# RPi_Zero_W_Breakout_0_3.net
KiCad netlist of a schematic drawn in EAGLE
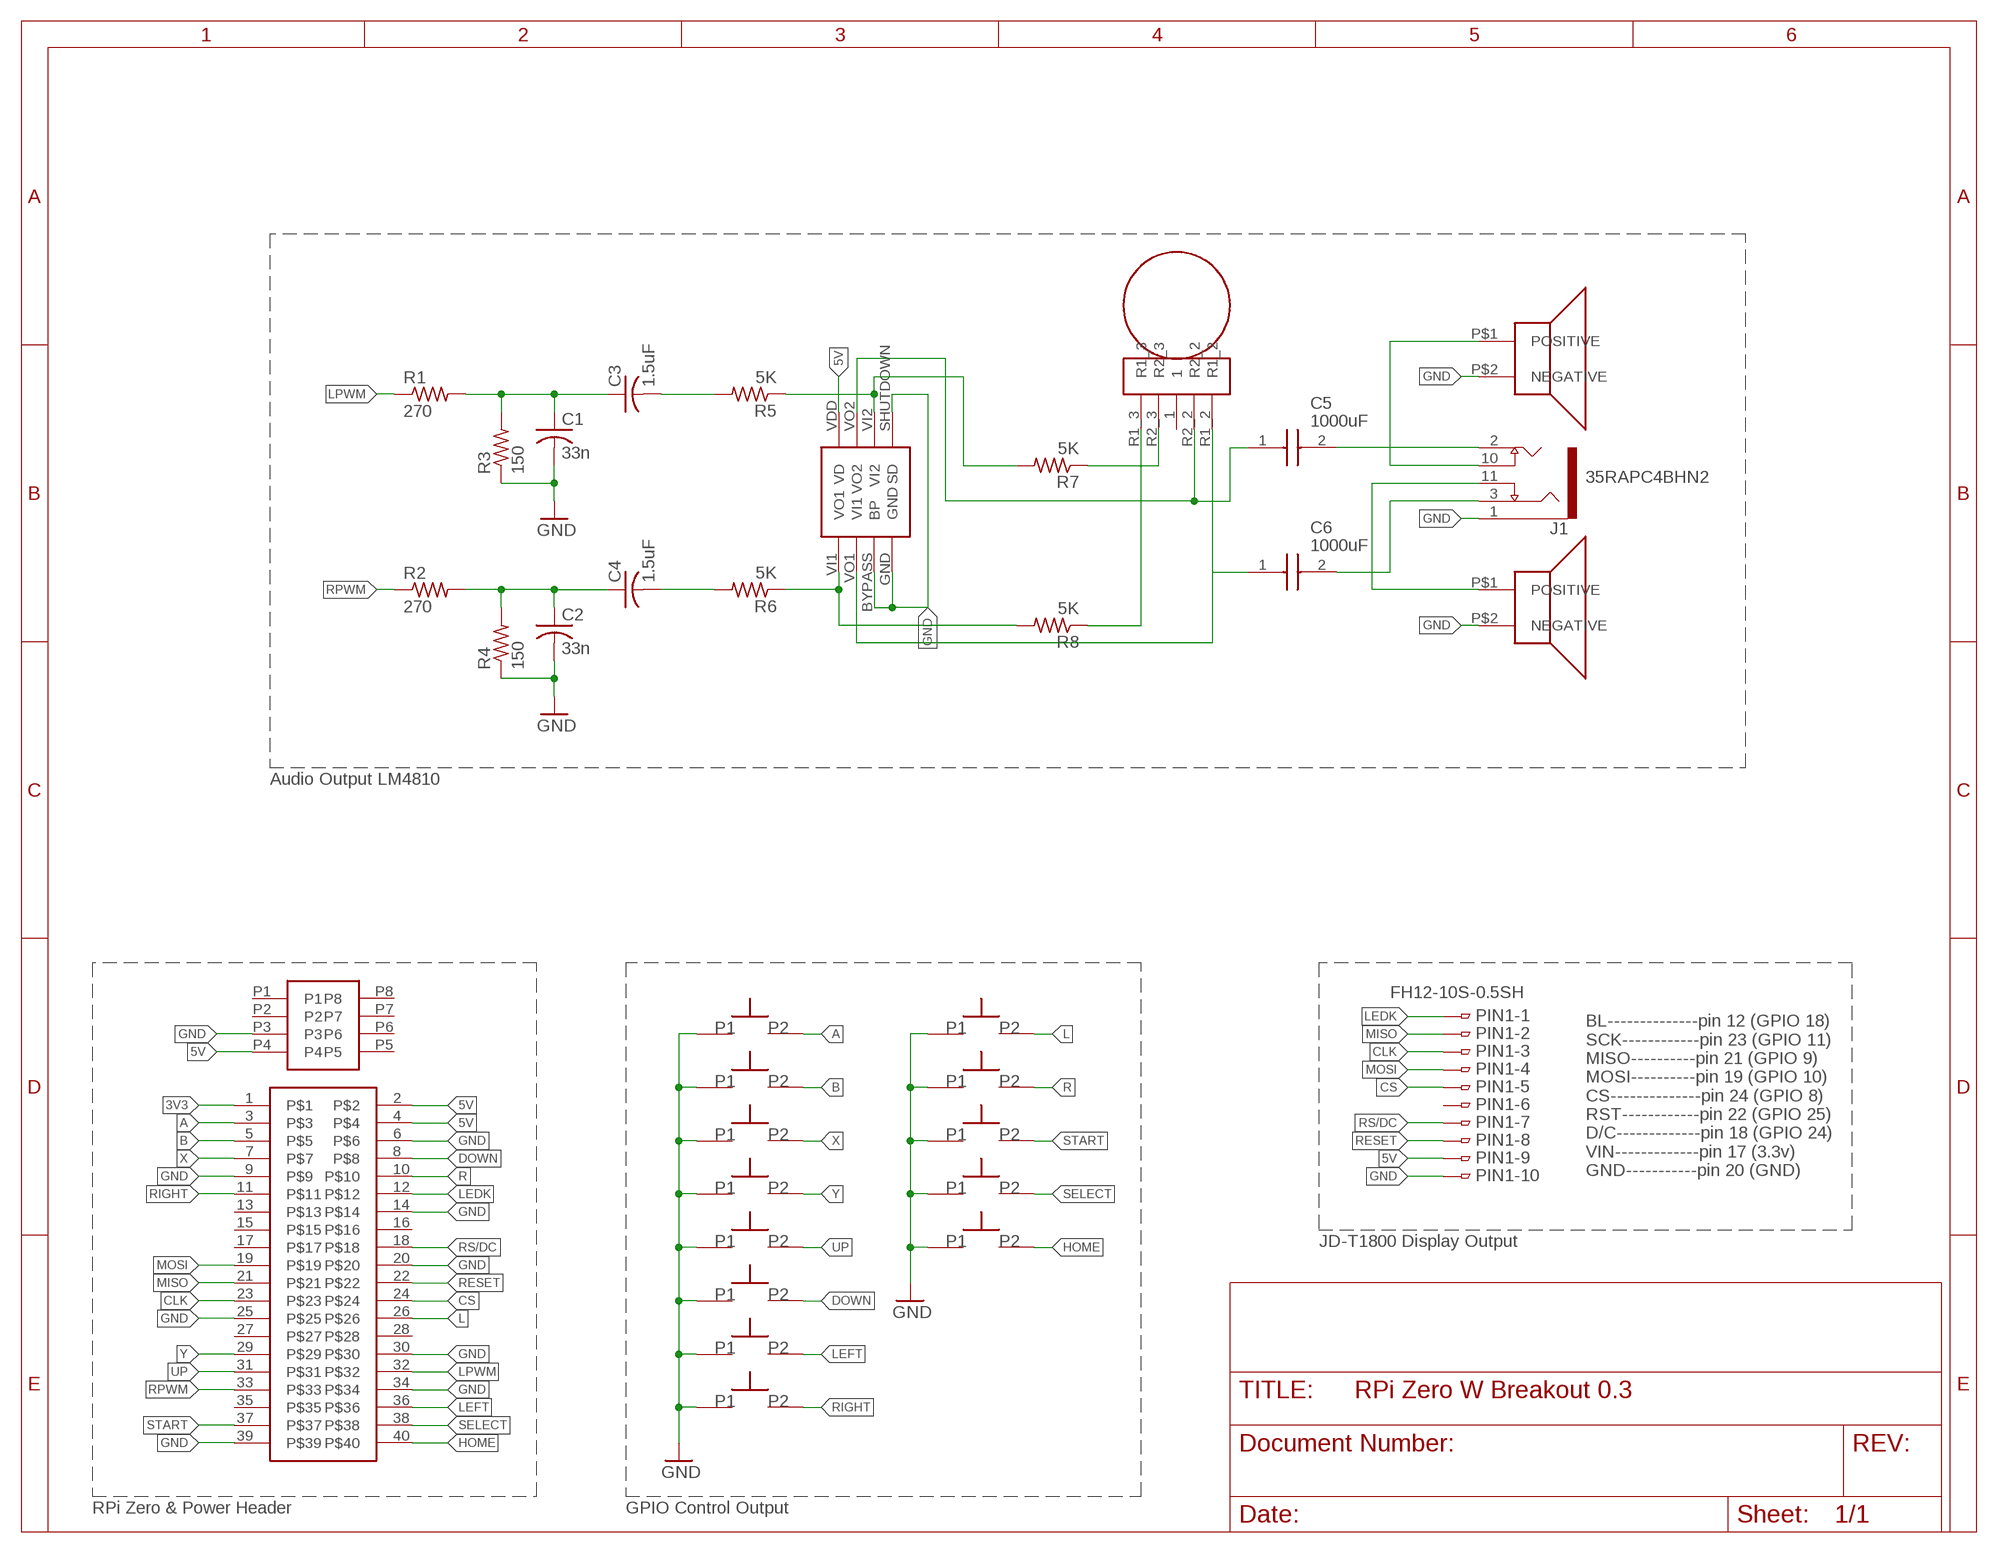
[diagram p0: schematic, sheet 1]

(export (version "E")
  (design (tool "Eeschema 10.0.6"))
  (components
    (comp (ref "A")
      (value "SPST_TACTILE_SWITCH")
      (footprint "eagle-import:SPST_TACTILESWITCH_TL3301PF160QG")
      (libsource (lib "eagle-import") (part "SPST_TACTILE_SWITCH"))
    )
    (comp (ref "B")
      (value "SPST_TACTILESWITCH_TL3301PF160QG")
      (footprint "eagle-import:SPST_TACTILESWITCH_TL3301PF160QG")
      (libsource (lib "eagle-import") (part "SPST_TACTILESWITCH_TL3301PF160QG"))
    )
    (comp (ref "C1")
      (value "33n")
      (footprint "eagle-import:C0805K")
      (libsource (lib "eagle-import") (part "C-USC0805K"))
    )
    (comp (ref "C2")
      (value "33n")
      (footprint "eagle-import:C0805K")
      (libsource (lib "eagle-import") (part "C-USC0805K"))
    )
    (comp (ref "C3")
      (value "1.5uF")
      (footprint "eagle-import:C0805K")
      (libsource (lib "eagle-import") (part "C-USC0805K"))
    )
    (comp (ref "C4")
      (value "1.5uF")
      (footprint "eagle-import:C0805K")
      (libsource (lib "eagle-import") (part "C-USC0805K"))
    )
    (comp (ref "C5")
      (value "1000uF")
      (footprint "eagle-import:UWT(8X10)")
      (fields
        (field (name "MANUFACTURER_PART_NUMBER") "UWT0J102MNL1GS")
        (field (name "MOUSER_PART_NUMBER") "647-UWT0J102MNL1S")
      )
      (libsource (lib "eagle-import") (part "UWT0J102MNL1GS"))
    )
    (comp (ref "C6")
      (value "1000uF")
      (footprint "eagle-import:UWT(8X10)")
      (fields
        (field (name "MANUFACTURER_PART_NUMBER") "UWT0J102MNL1GS")
        (field (name "MOUSER_PART_NUMBER") "647-UWT0J102MNL1S")
      )
      (libsource (lib "eagle-import") (part "UWT0J102MNL1GS"))
    )
    (comp (ref "DOWN")
      (value "SPST_TACTILESWITCH_TL3301PF160QG")
      (footprint "eagle-import:SPST_TACTILESWITCH_TL3301PF160QG")
      (libsource (lib "eagle-import") (part "SPST_TACTILESWITCH_TL3301PF160QG"))
    )
    (comp (ref "HOME")
      (value "SPST_TACTILESWITCH_TL3301PF160QG")
      (footprint "eagle-import:SPST_TACTILESWITCH_TL3301PF160QG")
      (libsource (lib "eagle-import") (part "SPST_TACTILESWITCH_TL3301PF160QG"))
    )
    (comp (ref "J1")
      (value "35RAPC4BHN2")
      (footprint "eagle-import:SWITCHCRAFT_35RAPC4BHN2")
      (fields (field (name "DIGI-KEY_PART_NUMBER") "SC1459-ND") (field (name "MF") "Switchcraft"))
      (libsource (lib "eagle-import") (part "35RAPC4BHN2"))
    )
    (comp (ref "LEFT")
      (value "SPST_TACTILESWITCH_TL3301PF160QG")
      (footprint "eagle-import:SPST_TACTILESWITCH_TL3301PF160QG")
      (libsource (lib "eagle-import") (part "SPST_TACTILESWITCH_TL3301PF160QG"))
    )
    (comp (ref "LSPK")
      (value "SP-1208")
      (footprint "eagle-import:SP-1208")
      (libsource (lib "eagle-import") (part "SP-1208"))
    )
    (comp (ref "PIN1")
      (value "FH12-10S-0.5SH")
      (footprint "eagle-import:FH12-10S-0.5SH")
      (fields (field (name "MPN") "FH12-10S-0.5SH(55)"))
      (libsource (lib "eagle-import") (part "FH12-10S-0.5SH"))
    )
    (comp (ref "R1")
      (value "270")
      (footprint "eagle-import:R0805")
      (libsource (lib "eagle-import") (part "R-US_R0805"))
    )
    (comp (ref "R2")
      (value "270")
      (footprint "eagle-import:R0805")
      (libsource (lib "eagle-import") (part "R-US_R0805"))
    )
    (comp (ref "R3")
      (value "150")
      (footprint "eagle-import:R0805")
      (libsource (lib "eagle-import") (part "R-US_R0805"))
    )
    (comp (ref "R4")
      (value "150")
      (footprint "eagle-import:R0805")
      (libsource (lib "eagle-import") (part "R-US_R0805"))
    )
    (comp (ref "R5")
      (value "5K")
      (footprint "eagle-import:R0805")
      (libsource (lib "eagle-import") (part "R-US_R0805"))
    )
    (comp (ref "R6")
      (value "5K")
      (footprint "eagle-import:R0805")
      (libsource (lib "eagle-import") (part "R-US_R0805"))
    )
    (comp (ref "R7")
      (value "5K")
      (footprint "eagle-import:R0805")
      (libsource (lib "eagle-import") (part "R-US_R0805"))
    )
    (comp (ref "R8")
      (value "5K")
      (footprint "eagle-import:R0805")
      (libsource (lib "eagle-import") (part "R-US_R0805"))
    )
    (comp (ref "RF")
      (value "RK14J12A0A0K")
      (footprint "eagle-import:RK14J12A0A0K")
      (libsource (lib "eagle-import") (part "RK14J12A0A0K"))
    )
    (comp (ref "RIGHT")
      (value "SPST_TACTILESWITCH_TL3301PF160QG")
      (footprint "eagle-import:SPST_TACTILESWITCH_TL3301PF160QG")
      (libsource (lib "eagle-import") (part "SPST_TACTILESWITCH_TL3301PF160QG"))
    )
    (comp (ref "RSPK")
      (value "SP-1208")
      (footprint "eagle-import:SP-1208")
      (libsource (lib "eagle-import") (part "SP-1208"))
    )
    (comp (ref "SELECT")
      (value "SPST_TACTILESWITCH_TL3301PF160QG")
      (footprint "eagle-import:SPST_TACTILESWITCH_TL3301PF160QG")
      (libsource (lib "eagle-import") (part "SPST_TACTILESWITCH_TL3301PF160QG"))
    )
    (comp (ref "START")
      (value "SPST_TACTILE_SWITCH")
      (footprint "eagle-import:SPST_TACTILESWITCH_TL3301PF160QG")
      (libsource (lib "eagle-import") (part "SPST_TACTILE_SWITCH"))
    )
    (comp (ref "U$1")
      (value "RPI_ZERO")
      (footprint "eagle-import:RPI_ZERO")
      (libsource (lib "eagle-import") (part "RPI_ZERO"))
    )
    (comp (ref "U$2")
      (value "LM4810MM/NOPBCT-ND")
      (footprint "eagle-import:NOPBCT-ND")
      (libsource (lib "eagle-import") (part "LM4810MM/NOPBCT-ND"))
    )
    (comp (ref "U$3")
      (value "M22-6340442")
      (footprint "eagle-import:M22-6340442")
      (libsource (lib "eagle-import") (part "M22-6340442"))
    )
    (comp (ref "U$4")
      (value "SPST_TACTILE_SWITCHRIGHTANGLEBENT")
      (footprint "eagle-import:SPST_TACTILESWITCH_TL3360CF185Q_BENTFRAME")
      (fields (field (name "SPICEPREFIX") "B"))
      (libsource (lib "eagle-import") (part "SPST_TACTILE_SWITCHRIGHTANGLEBENT"))
    )
    (comp (ref "U$5")
      (value "SPST_TACTILE_SWITCHRIGHTANGLEBENT")
      (footprint "eagle-import:SPST_TACTILESWITCH_TL3360CF185Q_BENTFRAME")
      (fields (field (name "SPICEPREFIX") "B"))
      (libsource (lib "eagle-import") (part "SPST_TACTILE_SWITCHRIGHTANGLEBENT"))
    )
    (comp (ref "UP")
      (value "SPST_TACTILESWITCH_TL3301PF160QG")
      (footprint "eagle-import:SPST_TACTILESWITCH_TL3301PF160QG")
      (libsource (lib "eagle-import") (part "SPST_TACTILESWITCH_TL3301PF160QG"))
    )
    (comp (ref "X")
      (value "SPST_TACTILESWITCH_TL3301PF160QG")
      (footprint "eagle-import:SPST_TACTILESWITCH_TL3301PF160QG")
      (libsource (lib "eagle-import") (part "SPST_TACTILESWITCH_TL3301PF160QG"))
    )
    (comp (ref "Y")
      (value "SPST_TACTILESWITCH_TL3301PF160QG")
      (footprint "eagle-import:SPST_TACTILESWITCH_TL3301PF160QG")
      (libsource (lib "eagle-import") (part "SPST_TACTILESWITCH_TL3301PF160QG"))
    )
  )
  (nets
    (net (code "1") (name "3V3") (class "Default")
      (node (ref "U$1") (pin "1") (pinfunction "P$1_1") (pintype "bidirectional"))
    )
    (net (code "2") (name "5V") (class "Default")
      (node (ref "PIN1") (pin "9") (pinfunction "1_9") (pintype "passive"))
      (node (ref "U$1") (pin "2") (pinfunction "P$2_2") (pintype "bidirectional"))
      (node (ref "U$1") (pin "4") (pinfunction "P$4_4") (pintype "bidirectional"))
      (node (ref "U$2") (pin "VDD") (pinfunction "VD_VDD") (pintype "bidirectional"))
      (node (ref "U$3") (pin "P4") (pinfunction "P4_P4") (pintype "bidirectional"))
    )
    (net (code "3") (name "A") (class "Default")
      (node (ref "A") (pin "P$3") (pinfunction "P$2_P$3") (pintype "bidirectional"))
      (node (ref "U$1") (pin "3") (pinfunction "P$3_3") (pintype "bidirectional"))
    )
    (net (code "4") (name "B") (class "Default")
      (node (ref "B") (pin "P$3") (pinfunction "P$2_P$3") (pintype "bidirectional"))
      (node (ref "U$1") (pin "5") (pinfunction "P$5_5") (pintype "bidirectional"))
    )
    (net (code "5") (name "CLK") (class "Default")
      (node (ref "PIN1") (pin "3") (pinfunction "1_3") (pintype "passive"))
      (node (ref "U$1") (pin "23") (pinfunction "P$23_23") (pintype "bidirectional"))
    )
    (net (code "6") (name "CS") (class "Default")
      (node (ref "PIN1") (pin "5") (pinfunction "1_5") (pintype "passive"))
      (node (ref "U$1") (pin "24") (pinfunction "P$24_24") (pintype "bidirectional"))
    )
    (net (code "7") (name "DOWN") (class "Default")
      (node (ref "DOWN") (pin "P$3") (pinfunction "P$2_P$3") (pintype "bidirectional"))
      (node (ref "U$1") (pin "8") (pinfunction "P$8_8") (pintype "bidirectional"))
    )
    (net (code "8") (name "GND") (class "Default")
      (node (ref "A") (pin "P$1") (pinfunction "P$1_P$1") (pintype "bidirectional"))
      (node (ref "B") (pin "P$1") (pinfunction "P$1_P$1") (pintype "bidirectional"))
      (node (ref "C1") (pin "2") (pinfunction "2_2") (pintype "passive"))
      (node (ref "C2") (pin "2") (pinfunction "2_2") (pintype "passive"))
      (node (ref "DOWN") (pin "P$1") (pinfunction "P$1_P$1") (pintype "bidirectional"))
      (node (ref "HOME") (pin "P$1") (pinfunction "P$1_P$1") (pintype "bidirectional"))
      (node (ref "J1") (pin "1") (pinfunction "1_1") (pintype "passive"))
      (node (ref "LEFT") (pin "P$1") (pinfunction "P$1_P$1") (pintype "bidirectional"))
      (node (ref "LSPK") (pin "P$2") (pinfunction "NEGATIVE_P$2") (pintype "bidirectional"))
      (node (ref "PIN1") (pin "10") (pinfunction "1_10") (pintype "passive"))
      (node (ref "R3") (pin "1") (pinfunction "1_1") (pintype "passive"))
      (node (ref "R4") (pin "1") (pinfunction "1_1") (pintype "passive"))
      (node (ref "RIGHT") (pin "P$1") (pinfunction "P$1_P$1") (pintype "bidirectional"))
      (node (ref "RSPK") (pin "P$2") (pinfunction "NEGATIVE_P$2") (pintype "bidirectional"))
      (node (ref "SELECT") (pin "P$1") (pinfunction "P$1_P$1") (pintype "bidirectional"))
      (node (ref "START") (pin "P$1") (pinfunction "P$1_P$1") (pintype "bidirectional"))
      (node (ref "U$1") (pin "14") (pinfunction "P$14_14") (pintype "bidirectional"))
      (node (ref "U$1") (pin "20") (pinfunction "P$20_20") (pintype "bidirectional"))
      (node (ref "U$1") (pin "25") (pinfunction "P$25_25") (pintype "bidirectional"))
      (node (ref "U$1") (pin "30") (pinfunction "P$30_30") (pintype "bidirectional"))
      (node (ref "U$1") (pin "34") (pinfunction "P$34_34") (pintype "bidirectional"))
      (node (ref "U$1") (pin "39") (pinfunction "P$39_39") (pintype "bidirectional"))
      (node (ref "U$1") (pin "6") (pinfunction "P$6_6") (pintype "bidirectional"))
      (node (ref "U$1") (pin "9") (pinfunction "P$9_9") (pintype "bidirectional"))
      (node (ref "U$2") (pin "BYPASS") (pinfunction "BP_BYPASS") (pintype "bidirectional"))
      (node (ref "U$2") (pin "GND") (pinfunction "GND_GND") (pintype "bidirectional"))
      (node (ref "U$2") (pin "SHUTDOWN") (pinfunction "SD_SHUTDOWN") (pintype "bidirectional"))
      (node (ref "U$3") (pin "P3") (pinfunction "P3_P3") (pintype "bidirectional"))
      (node (ref "U$4") (pin "P$1") (pinfunction "P$1_P$1") (pintype "bidirectional"))
      (node (ref "U$5") (pin "P$1") (pinfunction "P$1_P$1") (pintype "bidirectional"))
      (node (ref "UP") (pin "P$1") (pinfunction "P$1_P$1") (pintype "bidirectional"))
      (node (ref "X") (pin "P$1") (pinfunction "P$1_P$1") (pintype "bidirectional"))
      (node (ref "Y") (pin "P$1") (pinfunction "P$1_P$1") (pintype "bidirectional"))
    )
    (net (code "9") (name "HOME") (class "Default")
      (node (ref "HOME") (pin "P$3") (pinfunction "P$2_P$3") (pintype "bidirectional"))
      (node (ref "U$1") (pin "40") (pinfunction "P$40_40") (pintype "bidirectional"))
    )
    (net (code "10") (name "L") (class "Default")
      (node (ref "U$1") (pin "26") (pinfunction "P$26_26") (pintype "bidirectional"))
      (node (ref "U$4") (pin "P$2") (pinfunction "P$2_P$2") (pintype "bidirectional"))
    )
    (net (code "11") (name "LEDK") (class "Default")
      (node (ref "PIN1") (pin "1") (pinfunction "1_1") (pintype "passive"))
      (node (ref "U$1") (pin "12") (pinfunction "P$12_12") (pintype "bidirectional"))
    )
    (net (code "12") (name "LEFT") (class "Default")
      (node (ref "LEFT") (pin "P$3") (pinfunction "P$2_P$3") (pintype "bidirectional"))
      (node (ref "U$1") (pin "36") (pinfunction "P$36_36") (pintype "bidirectional"))
    )
    (net (code "13") (name "LPWM") (class "Default")
      (node (ref "R1") (pin "1") (pinfunction "1_1") (pintype "passive"))
      (node (ref "U$1") (pin "32") (pinfunction "P$32_32") (pintype "bidirectional"))
    )
    (net (code "14") (name "MISO") (class "Default")
      (node (ref "PIN1") (pin "2") (pinfunction "1_2") (pintype "passive"))
      (node (ref "U$1") (pin "21") (pinfunction "P$21_21") (pintype "bidirectional"))
    )
    (net (code "15") (name "MOSI") (class "Default")
      (node (ref "PIN1") (pin "4") (pinfunction "1_4") (pintype "passive"))
      (node (ref "U$1") (pin "19") (pinfunction "P$19_19") (pintype "bidirectional"))
    )
    (net (code "16") (name "Net-(C1-Pad1)") (class "Default")
      (node (ref "C1") (pin "1") (pinfunction "1_1") (pintype "passive"))
      (node (ref "C3") (pin "1") (pinfunction "1_1") (pintype "passive"))
      (node (ref "R1") (pin "2") (pinfunction "2_2") (pintype "passive"))
      (node (ref "R3") (pin "2") (pinfunction "2_2") (pintype "passive"))
    )
    (net (code "17") (name "Net-(C2-Pad1)") (class "Default")
      (node (ref "C2") (pin "1") (pinfunction "1_1") (pintype "passive"))
      (node (ref "C4") (pin "1") (pinfunction "1_1") (pintype "passive"))
      (node (ref "R2") (pin "2") (pinfunction "2_2") (pintype "passive"))
      (node (ref "R4") (pin "2") (pinfunction "2_2") (pintype "passive"))
    )
    (net (code "18") (name "Net-(C3-Pad2)") (class "Default")
      (node (ref "C3") (pin "2") (pinfunction "2_2") (pintype "passive"))
      (node (ref "R5") (pin "2") (pinfunction "2_2") (pintype "passive"))
    )
    (net (code "19") (name "Net-(C4-Pad2)") (class "Default")
      (node (ref "C4") (pin "2") (pinfunction "2_2") (pintype "passive"))
      (node (ref "R6") (pin "2") (pinfunction "2_2") (pintype "passive"))
    )
    (net (code "20") (name "Net-(C5-+)") (class "Default")
      (node (ref "C5") (pin "1") (pinfunction "+_1") (pintype "bidirectional"))
      (node (ref "RF") (pin "R2_2") (pinfunction "R2_2_R2_2") (pintype "bidirectional"))
      (node (ref "U$2") (pin "VO2") (pinfunction "VO2_VO2") (pintype "bidirectional"))
    )
    (net (code "21") (name "Net-(C5--)") (class "Default")
      (node (ref "C5") (pin "2") (pinfunction "-_2") (pintype "bidirectional"))
      (node (ref "J1") (pin "2") (pinfunction "2_2") (pintype "passive"))
    )
    (net (code "22") (name "Net-(C6-+)") (class "Default")
      (node (ref "C6") (pin "1") (pinfunction "+_1") (pintype "bidirectional"))
      (node (ref "RF") (pin "R1_2") (pinfunction "R1_2_R1_2") (pintype "bidirectional"))
      (node (ref "U$2") (pin "VO1") (pinfunction "VI1_VO1") (pintype "bidirectional"))
    )
    (net (code "23") (name "Net-(C6--)") (class "Default")
      (node (ref "C6") (pin "2") (pinfunction "-_2") (pintype "bidirectional"))
      (node (ref "J1") (pin "3") (pinfunction "3_3") (pintype "passive"))
    )
    (net (code "24") (name "Net-(LSPK-POSITIVE)") (class "Default")
      (node (ref "J1") (pin "10") (pinfunction "10_10") (pintype "passive"))
      (node (ref "LSPK") (pin "P$1") (pinfunction "POSITIVE_P$1") (pintype "bidirectional"))
    )
    (net (code "25") (name "Net-(R5-Pad1)") (class "Default")
      (node (ref "R5") (pin "1") (pinfunction "1_1") (pintype "passive"))
      (node (ref "R7") (pin "2") (pinfunction "2_2") (pintype "passive"))
      (node (ref "U$2") (pin "VI2") (pinfunction "VI2_VI2") (pintype "bidirectional"))
    )
    (net (code "26") (name "Net-(R7-Pad1)") (class "Default")
      (node (ref "R7") (pin "1") (pinfunction "1_1") (pintype "passive"))
      (node (ref "RF") (pin "R2_3") (pinfunction "R2_3_R2_3") (pintype "bidirectional"))
    )
    (net (code "27") (name "Net-(R8-Pad1)") (class "Default")
      (node (ref "R8") (pin "1") (pinfunction "1_1") (pintype "passive"))
      (node (ref "RF") (pin "R1_3") (pinfunction "R1_3_R1_3") (pintype "bidirectional"))
    )
    (net (code "28") (name "Net-(RSPK-POSITIVE)") (class "Default")
      (node (ref "J1") (pin "11") (pinfunction "11_11") (pintype "passive"))
      (node (ref "RSPK") (pin "P$1") (pinfunction "POSITIVE_P$1") (pintype "bidirectional"))
    )
    (net (code "29") (name "Net-(U$2-VO1)") (class "Default")
      (node (ref "R6") (pin "1") (pinfunction "1_1") (pintype "passive"))
      (node (ref "R8") (pin "2") (pinfunction "2_2") (pintype "passive"))
      (node (ref "U$2") (pin "VI1") (pinfunction "VO1_VI1") (pintype "bidirectional"))
    )
    (net (code "30") (name "R") (class "Default")
      (node (ref "U$1") (pin "10") (pinfunction "P$10_10") (pintype "bidirectional"))
      (node (ref "U$5") (pin "P$2") (pinfunction "P$2_P$2") (pintype "bidirectional"))
    )
    (net (code "31") (name "RESET") (class "Default")
      (node (ref "PIN1") (pin "8") (pinfunction "1_8") (pintype "passive"))
      (node (ref "U$1") (pin "22") (pinfunction "P$22_22") (pintype "bidirectional"))
    )
    (net (code "32") (name "RIGHT") (class "Default")
      (node (ref "RIGHT") (pin "P$3") (pinfunction "P$2_P$3") (pintype "bidirectional"))
      (node (ref "U$1") (pin "11") (pinfunction "P$11_11") (pintype "bidirectional"))
    )
    (net (code "33") (name "RPWM") (class "Default")
      (node (ref "R2") (pin "1") (pinfunction "1_1") (pintype "passive"))
      (node (ref "U$1") (pin "33") (pinfunction "P$33_33") (pintype "bidirectional"))
    )
    (net (code "34") (name "RS{slash}DC") (class "Default")
      (node (ref "PIN1") (pin "7") (pinfunction "1_7") (pintype "passive"))
      (node (ref "U$1") (pin "18") (pinfunction "P$18_18") (pintype "bidirectional"))
    )
    (net (code "35") (name "SELECT") (class "Default")
      (node (ref "SELECT") (pin "P$3") (pinfunction "P$2_P$3") (pintype "bidirectional"))
      (node (ref "U$1") (pin "38") (pinfunction "P$38_38") (pintype "bidirectional"))
    )
    (net (code "36") (name "START") (class "Default")
      (node (ref "START") (pin "P$3") (pinfunction "P$2_P$3") (pintype "bidirectional"))
      (node (ref "U$1") (pin "37") (pinfunction "P$37_37") (pintype "bidirectional"))
    )
    (net (code "37") (name "UP") (class "Default")
      (node (ref "U$1") (pin "31") (pinfunction "P$31_31") (pintype "bidirectional"))
      (node (ref "UP") (pin "P$3") (pinfunction "P$2_P$3") (pintype "bidirectional"))
    )
    (net (code "38") (name "X") (class "Default")
      (node (ref "U$1") (pin "7") (pinfunction "P$7_7") (pintype "bidirectional"))
      (node (ref "X") (pin "P$3") (pinfunction "P$2_P$3") (pintype "bidirectional"))
    )
    (net (code "39") (name "Y") (class "Default")
      (node (ref "U$1") (pin "29") (pinfunction "P$29_29") (pintype "bidirectional"))
      (node (ref "Y") (pin "P$3") (pinfunction "P$2_P$3") (pintype "bidirectional"))
    )
    (net (code "40") (name "unconnected-(PIN1G-1-Pad6)") (class "Default")
      (node (ref "PIN1") (pin "6") (pinfunction "1_6") (pintype "passive"))
    )
    (net (code "41") (name "unconnected-(RF-Pad1)") (class "Default")
      (node (ref "RF") (pin "1") (pinfunction "1_1") (pintype "bidirectional"))
    )
    (net (code "42") (name "unconnected-(U$1-P$13-Pad13)") (class "Default")
      (node (ref "U$1") (pin "13") (pinfunction "P$13_13") (pintype "bidirectional"))
    )
    (net (code "43") (name "unconnected-(U$1-P$15-Pad15)") (class "Default")
      (node (ref "U$1") (pin "15") (pinfunction "P$15_15") (pintype "bidirectional"))
    )
    (net (code "44") (name "unconnected-(U$1-P$16-Pad16)") (class "Default")
      (node (ref "U$1") (pin "16") (pinfunction "P$16_16") (pintype "bidirectional"))
    )
    (net (code "45") (name "unconnected-(U$1-P$17-Pad17)") (class "Default")
      (node (ref "U$1") (pin "17") (pinfunction "P$17_17") (pintype "bidirectional"))
    )
    (net (code "46") (name "unconnected-(U$1-P$27-Pad27)") (class "Default")
      (node (ref "U$1") (pin "27") (pinfunction "P$27_27") (pintype "bidirectional"))
    )
    (net (code "47") (name "unconnected-(U$1-P$28-Pad28)") (class "Default")
      (node (ref "U$1") (pin "28") (pinfunction "P$28_28") (pintype "bidirectional"))
    )
    (net (code "48") (name "unconnected-(U$1-P$35-Pad35)") (class "Default")
      (node (ref "U$1") (pin "35") (pinfunction "P$35_35") (pintype "bidirectional"))
    )
    (net (code "49") (name "unconnected-(U$3-PadP1)") (class "Default")
      (node (ref "U$3") (pin "P1") (pinfunction "P1_P1") (pintype "bidirectional"))
    )
    (net (code "50") (name "unconnected-(U$3-PadP2)") (class "Default")
      (node (ref "U$3") (pin "P2") (pinfunction "P2_P2") (pintype "bidirectional"))
    )
    (net (code "51") (name "unconnected-(U$3-PadP5)") (class "Default")
      (node (ref "U$3") (pin "P5") (pinfunction "P5_P5") (pintype "bidirectional"))
    )
    (net (code "52") (name "unconnected-(U$3-PadP6)") (class "Default")
      (node (ref "U$3") (pin "P6") (pinfunction "P6_P6") (pintype "bidirectional"))
    )
    (net (code "53") (name "unconnected-(U$3-PadP7)") (class "Default")
      (node (ref "U$3") (pin "P7") (pinfunction "P7_P7") (pintype "bidirectional"))
    )
    (net (code "54") (name "unconnected-(U$3-PadP8)") (class "Default")
      (node (ref "U$3") (pin "P8") (pinfunction "P8_P8") (pintype "bidirectional"))
    )
  )
)
